# Sensor_DS18b20_1Wire.net
KiCad netlist of a schematic drawn in Altium Designer
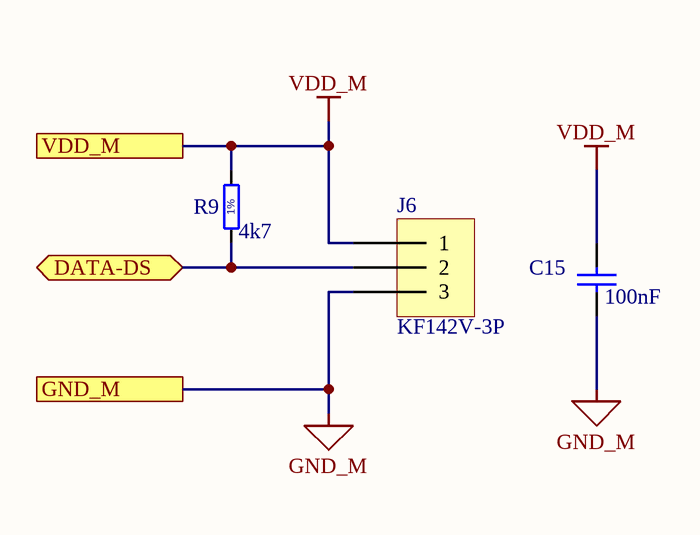
[diagram p0: Sensor_DS18b20_1Wire.SchDoc]

(export (version "E")
  (design (tool "Eeschema 10.0.6"))
  (components
    (comp (ref "C15")
      (value "100nF")
      (footprint "CAPC1608X87N")
      (description "Non-polarised capacitor")
      (fields
        (field (name "PART NUMBER") "CC0603_100NF_50V_10%_X7R")
        (field (name "VOLTAGE") "50V")
        (field (name "AUTHOR") "CERN DEM JLC")
      )
      (libsource (lib "Capacitors") (part "Capacitor - non polarized"))
    )
    (comp (ref "J6")
      (value "KF142V-3P")
      (footprint "CON KF142V-3P-5.08")
      (description "CON KF142V-3P-5.08")
      (libsource (lib "alib_pnphien") (part "CON KF142V-3P-5.08"))
    )
    (comp (ref "R9")
      (value "4k7")
      (footprint "RESC1608X55N")
      (description "Resistor - 1%")
      (fields
        (field (name "PART NUMBER") "R0603_4K7_1%_0.1W_100PPM")
        (field (name "POWER") "0.1W")
        (field (name "AUTHOR") "CERN DEM JLC")
      )
      (libsource (lib "Resistors") (part "Resistor - 1%"))
    )
  )
  (nets
    (net (code "1") (name "/DATA-DS") (class "Default")
      (node (ref "J6") (pin "2") (pinfunction "2_2") (pintype "passive"))
      (node (ref "R9") (pin "1") (pinfunction "1_1") (pintype "passive"))
    )
    (net (code "2") (name "GND_M") (class "Default")
      (node (ref "C15") (pin "1") (pinfunction "1_1") (pintype "passive"))
      (node (ref "J6") (pin "3") (pinfunction "3_3") (pintype "passive"))
    )
    (net (code "3") (name "VDD_M") (class "Default")
      (node (ref "C15") (pin "2") (pinfunction "2_2") (pintype "passive"))
      (node (ref "J6") (pin "1") (pinfunction "1_1") (pintype "passive"))
      (node (ref "R9") (pin "2") (pinfunction "2_2") (pintype "passive"))
    )
  )
)
